# Breadboard_Power_Supply.net
KiCad netlist of a schematic drawn in EAGLE
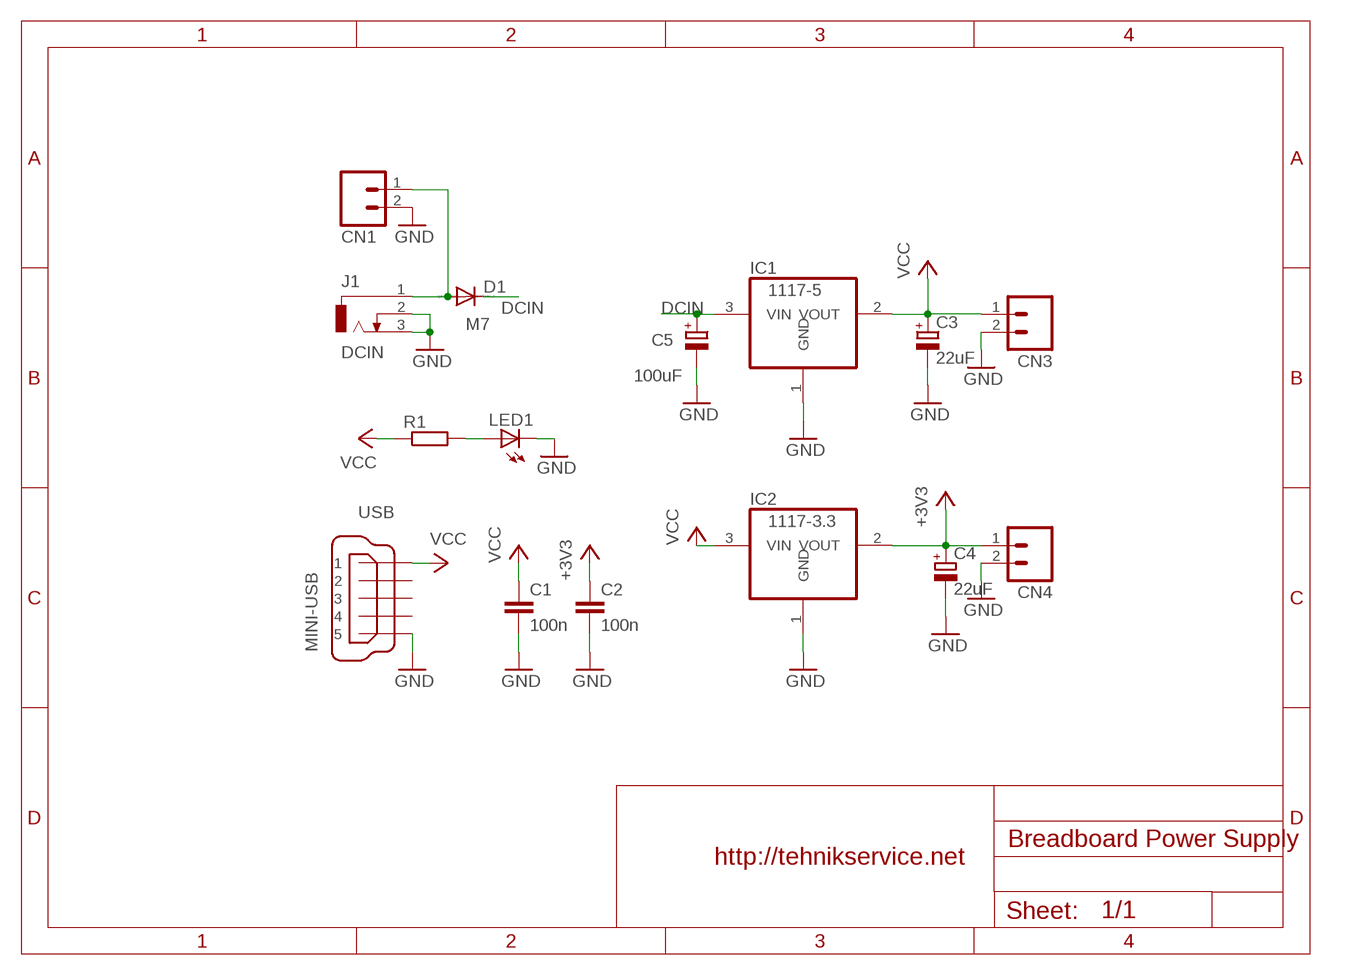
[diagram p0: schematic, sheet 1]

(export (version "E")
  (design (tool "Eeschema 10.0.6"))
  (components
    (comp (ref "C1")
      (value "100n")
      (footprint "eagle-import:C0805")
      (libsource (lib "eagle-import") (part "C-EUC0805"))
    )
    (comp (ref "C2")
      (value "100n")
      (footprint "eagle-import:C0805")
      (libsource (lib "eagle-import") (part "C-EUC0805"))
    )
    (comp (ref "C3")
      (value "22uF")
      (footprint "eagle-import:E2,5-5")
      (libsource (lib "eagle-import") (part "CPOL-EUE2.5-5"))
    )
    (comp (ref "C4")
      (value "22uF")
      (footprint "eagle-import:E2,5-5")
      (libsource (lib "eagle-import") (part "CPOL-EUE2.5-5"))
    )
    (comp (ref "C5")
      (value "100uF")
      (footprint "eagle-import:E2,5-5")
      (libsource (lib "eagle-import") (part "CPOL-EUE2.5-5"))
    )
    (comp (ref "CN1")
      (value "M02")
      (footprint "eagle-import:02P")
      (libsource (lib "eagle-import") (part "M02"))
    )
    (comp (ref "CN3")
      (value "M02")
      (footprint "eagle-import:02P")
      (libsource (lib "eagle-import") (part "M02"))
    )
    (comp (ref "CN4")
      (value "M02")
      (footprint "eagle-import:02P")
      (libsource (lib "eagle-import") (part "M02"))
    )
    (comp (ref "D1")
      (value "M7")
      (footprint "eagle-import:DO-214AC")
      (libsource (lib "eagle-import") (part "DIODE-DO-214AC"))
    )
    (comp (ref "IC1")
      (value "1117-5")
      (footprint "eagle-import:SOT223")
      (fields (field (name "MPN") "REG1117"))
      (libsource (lib "eagle-import") (part "REG1117"))
    )
    (comp (ref "IC2")
      (value "1117-3.3")
      (footprint "eagle-import:SOT223")
      (fields (field (name "MPN") "REG1117"))
      (libsource (lib "eagle-import") (part "REG1117"))
    )
    (comp (ref "J1")
      (value "DCIN")
      (footprint "eagle-import:DCJ0202")
      (libsource (lib "eagle-import") (part "DCJ0202"))
    )
    (comp (ref "LED1")
      (value "LEDCHIPLED_0805")
      (footprint "eagle-import:CHIPLED_0805")
      (libsource (lib "eagle-import") (part "LEDCHIPLED_0805"))
    )
    (comp (ref "R1")
      (value "R-EU_R0805")
      (footprint "eagle-import:R0805")
      (libsource (lib "eagle-import") (part "R-EU_R0805"))
    )
    (comp (ref "USB")
      (value "MINI-USB")
      (footprint "eagle-import:32005-201")
      (libsource (lib "eagle-import") (part "MINI-USB-32005-201"))
    )
  )
  (nets
    (net (code "1") (name "+3V3") (class "Default")
      (node (ref "C2") (pin "1") (pinfunction "1_1") (pintype "passive"))
      (node (ref "C4") (pin "+") (pinfunction "+_+") (pintype "passive"))
      (node (ref "CN4") (pin "1") (pinfunction "1_1") (pintype "passive"))
      (node (ref "IC2") (pin "2") (pinfunction "VOUT_2") (pintype "output"))
    )
    (net (code "2") (name "/DCIN") (class "Default")
      (node (ref "C5") (pin "+") (pinfunction "+_+") (pintype "passive"))
      (node (ref "D1") (pin "C") (pinfunction "C_C") (pintype "passive"))
      (node (ref "IC1") (pin "3") (pinfunction "VIN_3") (pintype "input"))
    )
    (net (code "3") (name "GND") (class "Default")
      (node (ref "C1") (pin "2") (pinfunction "2_2") (pintype "passive"))
      (node (ref "C2") (pin "2") (pinfunction "2_2") (pintype "passive"))
      (node (ref "C3") (pin "-") (pinfunction "-_-") (pintype "passive"))
      (node (ref "C4") (pin "-") (pinfunction "-_-") (pintype "passive"))
      (node (ref "C5") (pin "-") (pinfunction "-_-") (pintype "passive"))
      (node (ref "CN1") (pin "2") (pinfunction "2_2") (pintype "passive"))
      (node (ref "CN3") (pin "2") (pinfunction "2_2") (pintype "passive"))
      (node (ref "CN4") (pin "2") (pinfunction "2_2") (pintype "passive"))
      (node (ref "IC1") (pin "1") (pinfunction "GND_1") (pintype "power_in"))
      (node (ref "IC2") (pin "1") (pinfunction "GND_1") (pintype "power_in"))
      (node (ref "J1") (pin "2") (pinfunction "2_2") (pintype "passive"))
      (node (ref "J1") (pin "3") (pinfunction "3_3") (pintype "passive"))
      (node (ref "LED1") (pin "C") (pinfunction "C_C") (pintype "passive"))
      (node (ref "USB") (pin "5") (pinfunction "5_5") (pintype "passive"))
    )
    (net (code "4") (name "Net-(CN1-Pad1)") (class "Default")
      (node (ref "CN1") (pin "1") (pinfunction "1_1") (pintype "passive"))
      (node (ref "D1") (pin "A") (pinfunction "A_A") (pintype "passive"))
      (node (ref "J1") (pin "1") (pinfunction "1_1") (pintype "passive"))
    )
    (net (code "5") (name "Net-(LED1-PadA)") (class "Default")
      (node (ref "LED1") (pin "A") (pinfunction "A_A") (pintype "passive"))
      (node (ref "R1") (pin "2") (pinfunction "2_2") (pintype "passive"))
    )
    (net (code "6") (name "VCC") (class "Default")
      (node (ref "C1") (pin "1") (pinfunction "1_1") (pintype "passive"))
      (node (ref "C3") (pin "+") (pinfunction "+_+") (pintype "passive"))
      (node (ref "CN3") (pin "1") (pinfunction "1_1") (pintype "passive"))
      (node (ref "IC1") (pin "2") (pinfunction "VOUT_2") (pintype "output"))
      (node (ref "IC2") (pin "3") (pinfunction "VIN_3") (pintype "input"))
      (node (ref "R1") (pin "1") (pinfunction "1_1") (pintype "passive"))
      (node (ref "USB") (pin "1") (pinfunction "1_1") (pintype "passive"))
    )
    (net (code "7") (name "unconnected-(USB-Pad2)") (class "Default")
      (node (ref "USB") (pin "2") (pinfunction "2_2") (pintype "passive"))
    )
    (net (code "8") (name "unconnected-(USB-Pad3)") (class "Default")
      (node (ref "USB") (pin "3") (pinfunction "3_3") (pintype "passive"))
    )
    (net (code "9") (name "unconnected-(USB-Pad4)") (class "Default")
      (node (ref "USB") (pin "4") (pinfunction "4_4") (pintype "passive"))
    )
  )
)
